# ATtinyMario_schematic_fullboard.net
KiCad netlist of a schematic drawn in EAGLE
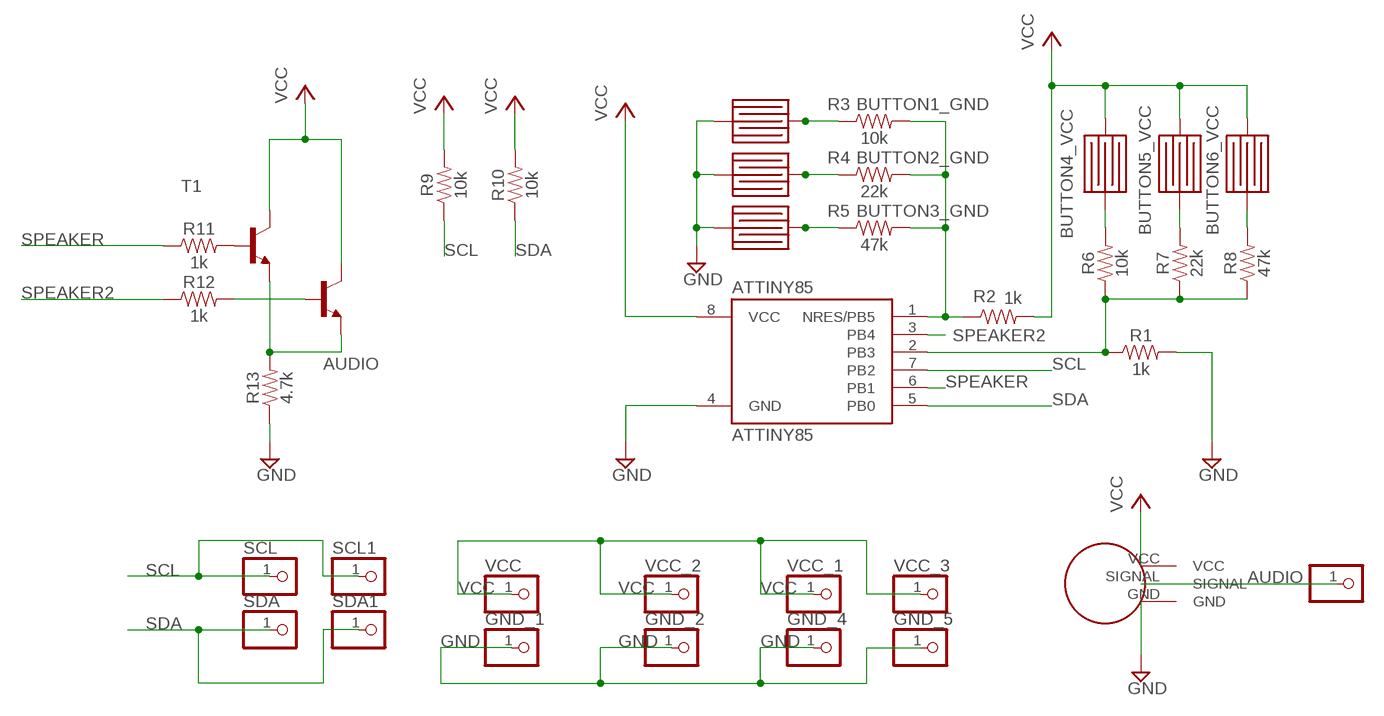
[diagram p0: schematic, sheet 1]

(export (version "E")
  (design (tool "Eeschema 10.0.6"))
  (components
    (comp (ref "ATTINY85")
      (value "ATTINY85")
      (footprint "eagle-import:PDIP08_300MIL")
      (libsource (lib "eagle-import") (part "ATTINY85P-20"))
    )
    (comp (ref "GND_1")
      (value "PINHD-1X1")
      (footprint "eagle-import:1X01")
      (libsource (lib "eagle-import") (part "PINHD-1X1"))
    )
    (comp (ref "GND_2")
      (value "PINHD-1X1")
      (footprint "eagle-import:1X01")
      (libsource (lib "eagle-import") (part "PINHD-1X1"))
    )
    (comp (ref "GND_3")
      (value "PINHD-1X1")
      (footprint "eagle-import:1X01")
      (libsource (lib "eagle-import") (part "PINHD-1X1"))
    )
    (comp (ref "GND_4")
      (value "PINHD-1X1")
      (footprint "eagle-import:1X01")
      (libsource (lib "eagle-import") (part "PINHD-1X1"))
    )
    (comp (ref "GND_5")
      (value "PINHD-1X1")
      (footprint "eagle-import:1X01")
      (libsource (lib "eagle-import") (part "PINHD-1X1"))
    )
    (comp (ref "R1")
      (value "1k")
      (footprint "eagle-import:AXIAL-0.3")
      (libsource (lib "eagle-import") (part "RESISTORAXIAL-0.3"))
    )
    (comp (ref "R2")
      (value "1k")
      (footprint "eagle-import:AXIAL-0.3")
      (libsource (lib "eagle-import") (part "RESISTORAXIAL-0.3"))
    )
    (comp (ref "R3")
      (value "10k")
      (footprint "eagle-import:AXIAL-0.3")
      (libsource (lib "eagle-import") (part "RESISTORAXIAL-0.3"))
    )
    (comp (ref "R4")
      (value "22k")
      (footprint "eagle-import:AXIAL-0.3")
      (libsource (lib "eagle-import") (part "RESISTORAXIAL-0.3"))
    )
    (comp (ref "R5")
      (value "47k")
      (footprint "eagle-import:AXIAL-0.3")
      (libsource (lib "eagle-import") (part "RESISTORAXIAL-0.3"))
    )
    (comp (ref "R6")
      (value "10k")
      (footprint "eagle-import:AXIAL-0.3")
      (libsource (lib "eagle-import") (part "RESISTORAXIAL-0.3"))
    )
    (comp (ref "R7")
      (value "22k")
      (footprint "eagle-import:AXIAL-0.3")
      (libsource (lib "eagle-import") (part "RESISTORAXIAL-0.3"))
    )
    (comp (ref "R8")
      (value "47k")
      (footprint "eagle-import:AXIAL-0.3")
      (libsource (lib "eagle-import") (part "RESISTORAXIAL-0.3"))
    )
    (comp (ref "R9")
      (value "10k")
      (footprint "eagle-import:AXIAL-0.3")
      (libsource (lib "eagle-import") (part "RESISTORAXIAL-0.3"))
    )
    (comp (ref "R10")
      (value "10k")
      (footprint "eagle-import:AXIAL-0.3")
      (libsource (lib "eagle-import") (part "RESISTORAXIAL-0.3"))
    )
    (comp (ref "R11")
      (value "1k")
      (footprint "eagle-import:AXIAL-0.3")
      (libsource (lib "eagle-import") (part "RESISTORAXIAL-0.3"))
    )
    (comp (ref "R12")
      (value "1k")
      (footprint "eagle-import:AXIAL-0.3")
      (libsource (lib "eagle-import") (part "RESISTORAXIAL-0.3"))
    )
    (comp (ref "R13")
      (value "4.7k")
      (footprint "eagle-import:AXIAL-0.3")
      (libsource (lib "eagle-import") (part "RESISTORAXIAL-0.3"))
    )
    (comp (ref "SCL")
      (value "PINHD-1X1CB")
      (footprint "eagle-import:1X01-CLEANBIG")
      (libsource (lib "eagle-import") (part "PINHD-1X1CB"))
    )
    (comp (ref "SCL1")
      (value "PINHD-1X1CB")
      (footprint "eagle-import:1X01-CLEANBIG")
      (libsource (lib "eagle-import") (part "PINHD-1X1CB"))
    )
    (comp (ref "SDA")
      (value "PINHD-1X1CB")
      (footprint "eagle-import:1X01-CLEANBIG")
      (libsource (lib "eagle-import") (part "PINHD-1X1CB"))
    )
    (comp (ref "SDA1")
      (value "PINHD-1X1CB")
      (footprint "eagle-import:1X01-CLEANBIG")
      (libsource (lib "eagle-import") (part "PINHD-1X1CB"))
    )
    (comp (ref "T1")
      (value "2N2222")
      (footprint "eagle-import:TO92-EBC-OVAL")
      (libsource (lib "eagle-import") (part "2N2222"))
    )
    (comp (ref "T2")
      (value "2N2222")
      (footprint "eagle-import:TO92-EBC-OVAL")
      (libsource (lib "eagle-import") (part "2N2222"))
    )
    (comp (ref "U$1")
      (value "PCB_BUTTON_DEVICE")
      (footprint "eagle-import:PCB_BUTTON")
      (libsource (lib "eagle-import") (part "PCB_BUTTON_DEVICE"))
    )
    (comp (ref "U$2")
      (value "PCB_BUTTON_DEVICE")
      (footprint "eagle-import:PCB_BUTTON")
      (libsource (lib "eagle-import") (part "PCB_BUTTON_DEVICE"))
    )
    (comp (ref "U$3")
      (value "PCB_BUTTON_DEVICE")
      (footprint "eagle-import:PCB_BUTTON")
      (libsource (lib "eagle-import") (part "PCB_BUTTON_DEVICE"))
    )
    (comp (ref "U$4")
      (value "PCB_BUTTON_DEVICE")
      (footprint "eagle-import:PCB_BUTTON")
      (libsource (lib "eagle-import") (part "PCB_BUTTON_DEVICE"))
    )
    (comp (ref "U$5")
      (value "VOLUME_WHEEL")
      (footprint "eagle-import:VOLUME_PCB")
      (libsource (lib "eagle-import") (part "VOLUME_WHEEL"))
    )
    (comp (ref "U$6")
      (value "PCB_BUTTON_DEVICE")
      (footprint "eagle-import:PCB_BUTTON")
      (libsource (lib "eagle-import") (part "PCB_BUTTON_DEVICE"))
    )
    (comp (ref "U$7")
      (value "PCB_BUTTON_DEVICE")
      (footprint "eagle-import:PCB_BUTTON")
      (libsource (lib "eagle-import") (part "PCB_BUTTON_DEVICE"))
    )
    (comp (ref "VCC")
      (value "PINHD-1X1")
      (footprint "eagle-import:1X01")
      (libsource (lib "eagle-import") (part "PINHD-1X1"))
    )
    (comp (ref "VCC_1")
      (value "PINHD-1X1")
      (footprint "eagle-import:1X01")
      (libsource (lib "eagle-import") (part "PINHD-1X1"))
    )
    (comp (ref "VCC_2")
      (value "PINHD-1X1")
      (footprint "eagle-import:1X01")
      (libsource (lib "eagle-import") (part "PINHD-1X1"))
    )
    (comp (ref "VCC_3")
      (value "PINHD-1X1")
      (footprint "eagle-import:1X01")
      (libsource (lib "eagle-import") (part "PINHD-1X1"))
    )
  )
  (nets
    (net (code "1") (name "/AUDIO") (class "Default")
      (node (ref "GND_3") (pin "1") (pinfunction "1_1") (pintype "passive"))
      (node (ref "R13") (pin "P$2") (pinfunction "2_P$2") (pintype "passive"))
      (node (ref "T1") (pin "E") (pinfunction "E_E") (pintype "passive"))
      (node (ref "T2") (pin "E") (pinfunction "E_E") (pintype "passive"))
      (node (ref "U$5") (pin "SIGNAL") (pinfunction "SIGNAL_SIGNAL") (pintype "bidirectional"))
    )
    (net (code "2") (name "/BUTTON1_GND") (class "Default")
      (node (ref "R3") (pin "P$1") (pinfunction "1_P$1") (pintype "passive"))
      (node (ref "U$1") (pin "PAD1") (pinfunction "PAD1_PAD1") (pintype "bidirectional"))
    )
    (net (code "3") (name "/BUTTON2_GND") (class "Default")
      (node (ref "R4") (pin "P$1") (pinfunction "1_P$1") (pintype "passive"))
      (node (ref "U$6") (pin "PAD1") (pinfunction "PAD1_PAD1") (pintype "bidirectional"))
    )
    (net (code "4") (name "/BUTTON3_GND") (class "Default")
      (node (ref "R5") (pin "P$1") (pinfunction "1_P$1") (pintype "passive"))
      (node (ref "U$7") (pin "PAD1") (pinfunction "PAD1_PAD1") (pintype "bidirectional"))
    )
    (net (code "5") (name "/BUTTON4_VCC") (class "Default")
      (node (ref "R6") (pin "P$2") (pinfunction "2_P$2") (pintype "passive"))
      (node (ref "U$2") (pin "PAD2") (pinfunction "PAD2_PAD2") (pintype "bidirectional"))
    )
    (net (code "6") (name "/BUTTON5_VCC") (class "Default")
      (node (ref "R7") (pin "P$2") (pinfunction "2_P$2") (pintype "passive"))
      (node (ref "U$3") (pin "PAD2") (pinfunction "PAD2_PAD2") (pintype "bidirectional"))
    )
    (net (code "7") (name "/BUTTON6_VCC") (class "Default")
      (node (ref "R8") (pin "P$2") (pinfunction "2_P$2") (pintype "passive"))
      (node (ref "U$4") (pin "PAD2") (pinfunction "PAD2_PAD2") (pintype "bidirectional"))
    )
    (net (code "8") (name "/SCL") (class "Default")
      (node (ref "ATTINY85") (pin "7") (pinfunction "PB2_7") (pintype "bidirectional"))
      (node (ref "R9") (pin "P$1") (pinfunction "1_P$1") (pintype "passive"))
      (node (ref "SCL") (pin "1") (pinfunction "1_1") (pintype "passive"))
      (node (ref "SCL1") (pin "1") (pinfunction "1_1") (pintype "passive"))
    )
    (net (code "9") (name "/SDA") (class "Default")
      (node (ref "ATTINY85") (pin "5") (pinfunction "PB0_5") (pintype "bidirectional"))
      (node (ref "R10") (pin "P$1") (pinfunction "1_P$1") (pintype "passive"))
      (node (ref "SDA") (pin "1") (pinfunction "1_1") (pintype "passive"))
      (node (ref "SDA1") (pin "1") (pinfunction "1_1") (pintype "passive"))
    )
    (net (code "10") (name "/SPEAKER") (class "Default")
      (node (ref "ATTINY85") (pin "6") (pinfunction "PB1_6") (pintype "bidirectional"))
      (node (ref "R11") (pin "P$1") (pinfunction "1_P$1") (pintype "passive"))
    )
    (net (code "11") (name "/SPEAKER2") (class "Default")
      (node (ref "ATTINY85") (pin "3") (pinfunction "PB4_3") (pintype "bidirectional"))
      (node (ref "R12") (pin "P$1") (pinfunction "1_P$1") (pintype "passive"))
    )
    (net (code "12") (name "GND") (class "Default")
      (node (ref "ATTINY85") (pin "4") (pinfunction "GND_4") (pintype "power_in"))
      (node (ref "GND_1") (pin "1") (pinfunction "1_1") (pintype "passive"))
      (node (ref "GND_2") (pin "1") (pinfunction "1_1") (pintype "passive"))
      (node (ref "GND_4") (pin "1") (pinfunction "1_1") (pintype "passive"))
      (node (ref "GND_5") (pin "1") (pinfunction "1_1") (pintype "passive"))
      (node (ref "R1") (pin "P$2") (pinfunction "2_P$2") (pintype "passive"))
      (node (ref "R13") (pin "P$1") (pinfunction "1_P$1") (pintype "passive"))
      (node (ref "U$1") (pin "PAD2") (pinfunction "PAD2_PAD2") (pintype "bidirectional"))
      (node (ref "U$5") (pin "GND") (pinfunction "GND_GND") (pintype "bidirectional"))
      (node (ref "U$6") (pin "PAD2") (pinfunction "PAD2_PAD2") (pintype "bidirectional"))
      (node (ref "U$7") (pin "PAD2") (pinfunction "PAD2_PAD2") (pintype "bidirectional"))
    )
    (net (code "13") (name "Net-(ATTINY85-NRES{slash}PB5)") (class "Default")
      (node (ref "ATTINY85") (pin "1") (pinfunction "NRES/PB5_1") (pintype "bidirectional"))
      (node (ref "R2") (pin "P$1") (pinfunction "1_P$1") (pintype "passive"))
      (node (ref "R3") (pin "P$2") (pinfunction "2_P$2") (pintype "passive"))
      (node (ref "R4") (pin "P$2") (pinfunction "2_P$2") (pintype "passive"))
      (node (ref "R5") (pin "P$2") (pinfunction "2_P$2") (pintype "passive"))
    )
    (net (code "14") (name "Net-(ATTINY85-PB3)") (class "Default")
      (node (ref "ATTINY85") (pin "2") (pinfunction "PB3_2") (pintype "bidirectional"))
      (node (ref "R1") (pin "P$1") (pinfunction "1_P$1") (pintype "passive"))
      (node (ref "R6") (pin "P$1") (pinfunction "1_P$1") (pintype "passive"))
      (node (ref "R7") (pin "P$1") (pinfunction "1_P$1") (pintype "passive"))
      (node (ref "R8") (pin "P$1") (pinfunction "1_P$1") (pintype "passive"))
    )
    (net (code "15") (name "Net-(R11-2)") (class "Default")
      (node (ref "R11") (pin "P$2") (pinfunction "2_P$2") (pintype "passive"))
      (node (ref "T1") (pin "B") (pinfunction "B_B") (pintype "passive"))
    )
    (net (code "16") (name "Net-(R12-2)") (class "Default")
      (node (ref "R12") (pin "P$2") (pinfunction "2_P$2") (pintype "passive"))
      (node (ref "T2") (pin "B") (pinfunction "B_B") (pintype "passive"))
    )
    (net (code "17") (name "VCC") (class "Default")
      (node (ref "ATTINY85") (pin "8") (pinfunction "VCC_8") (pintype "power_in"))
      (node (ref "R10") (pin "P$2") (pinfunction "2_P$2") (pintype "passive"))
      (node (ref "R2") (pin "P$2") (pinfunction "2_P$2") (pintype "passive"))
      (node (ref "R9") (pin "P$2") (pinfunction "2_P$2") (pintype "passive"))
      (node (ref "T1") (pin "C") (pinfunction "C_C") (pintype "passive"))
      (node (ref "T2") (pin "C") (pinfunction "C_C") (pintype "passive"))
      (node (ref "U$2") (pin "PAD1") (pinfunction "PAD1_PAD1") (pintype "bidirectional"))
      (node (ref "U$3") (pin "PAD1") (pinfunction "PAD1_PAD1") (pintype "bidirectional"))
      (node (ref "U$4") (pin "PAD1") (pinfunction "PAD1_PAD1") (pintype "bidirectional"))
      (node (ref "U$5") (pin "VCC") (pinfunction "VCC_VCC") (pintype "bidirectional"))
      (node (ref "VCC") (pin "1") (pinfunction "1_1") (pintype "passive"))
      (node (ref "VCC_1") (pin "1") (pinfunction "1_1") (pintype "passive"))
      (node (ref "VCC_2") (pin "1") (pinfunction "1_1") (pintype "passive"))
      (node (ref "VCC_3") (pin "1") (pinfunction "1_1") (pintype "passive"))
    )
  )
)
